# untitled.net
KiCad netlist of a schematic drawn in EAGLE
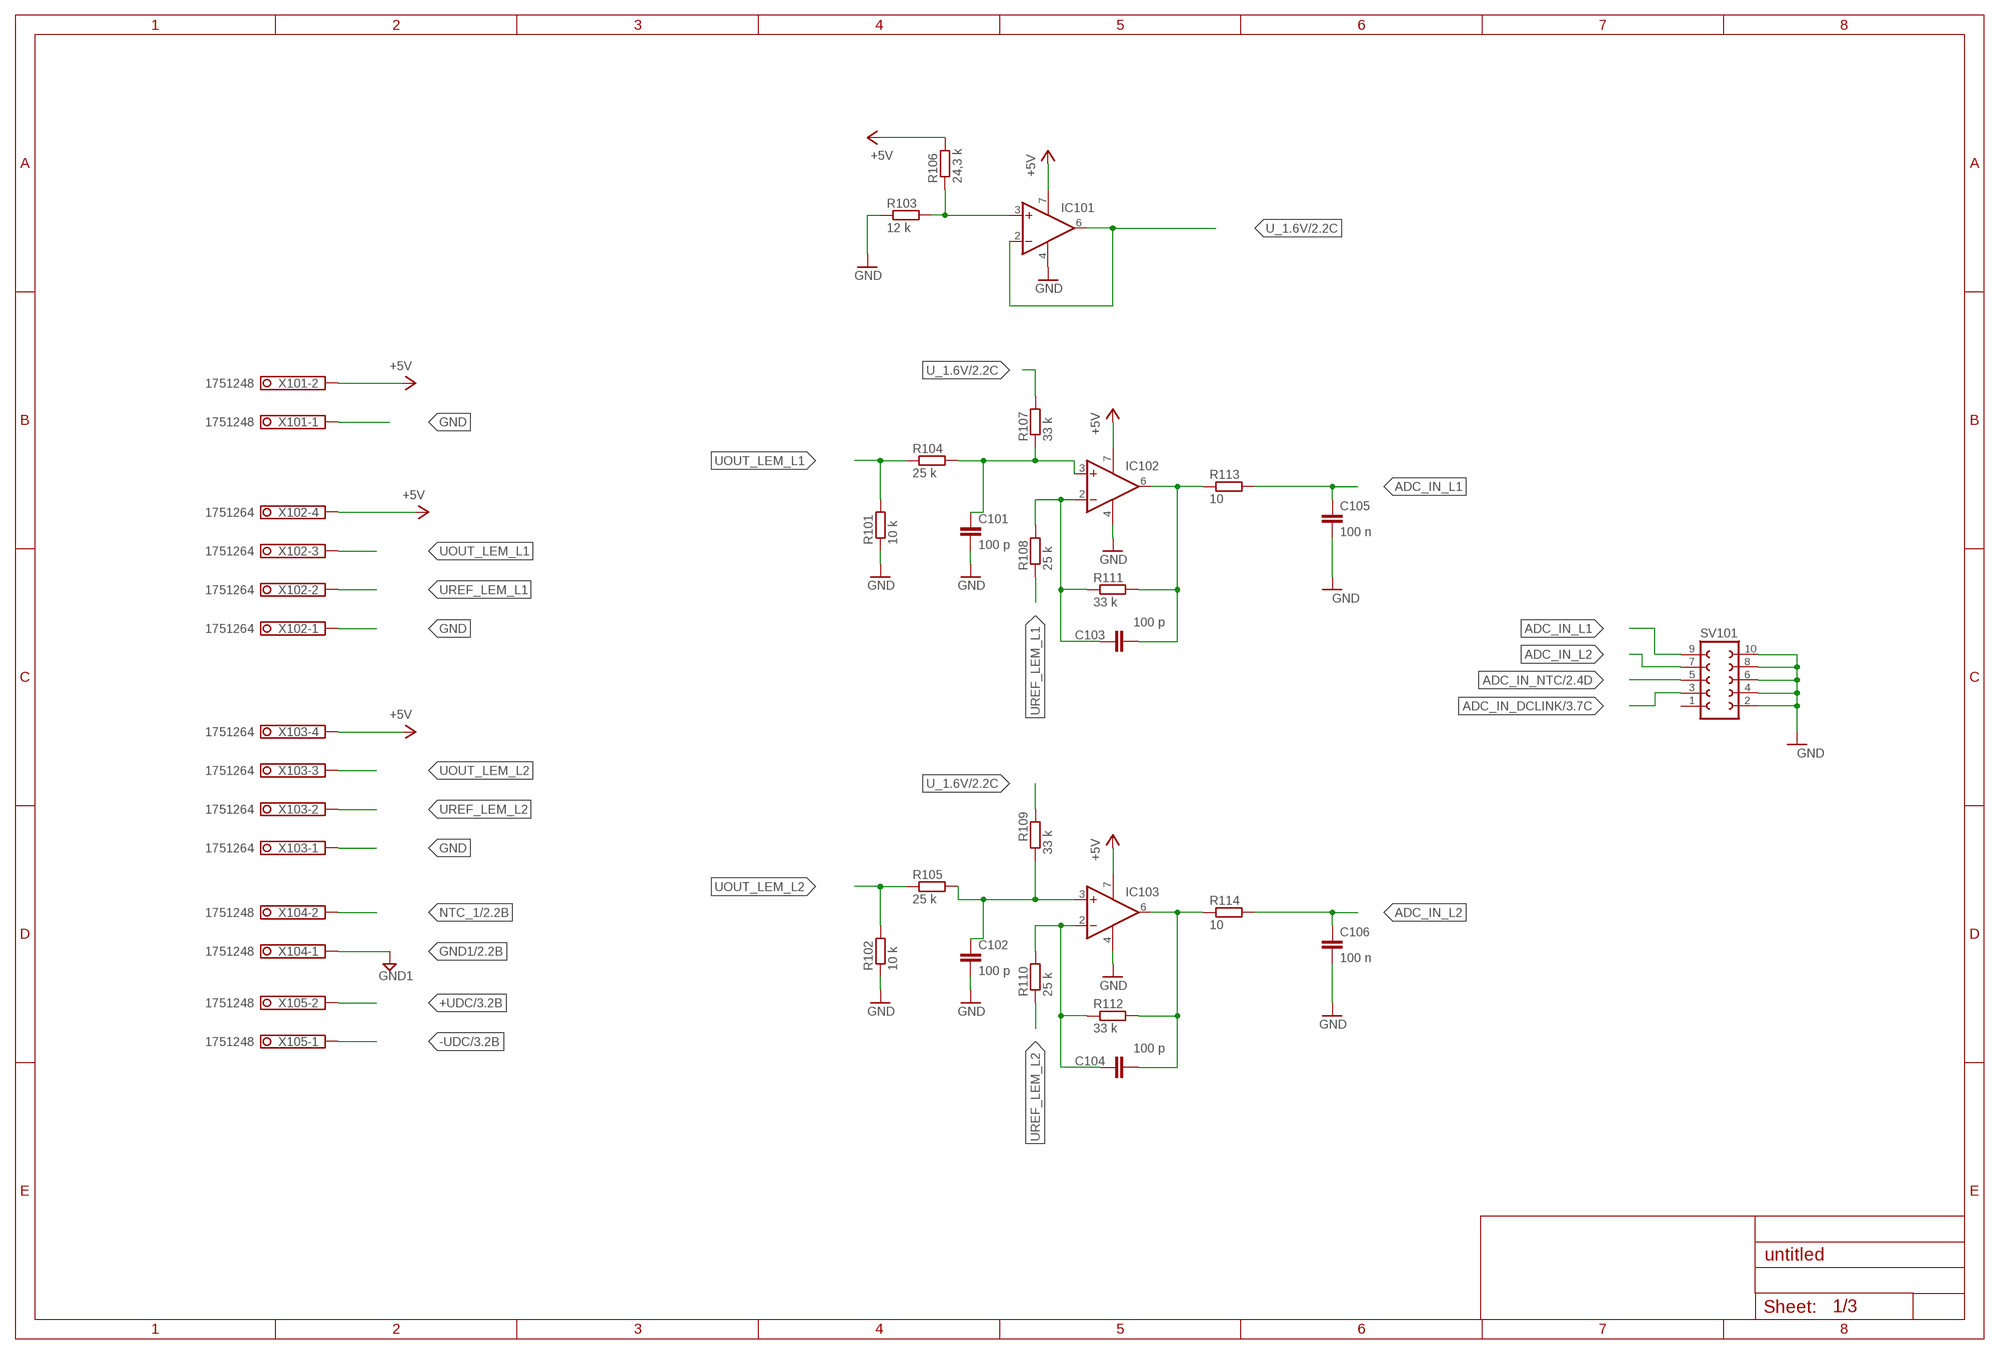
[diagram p0: schematic, sheet 1]
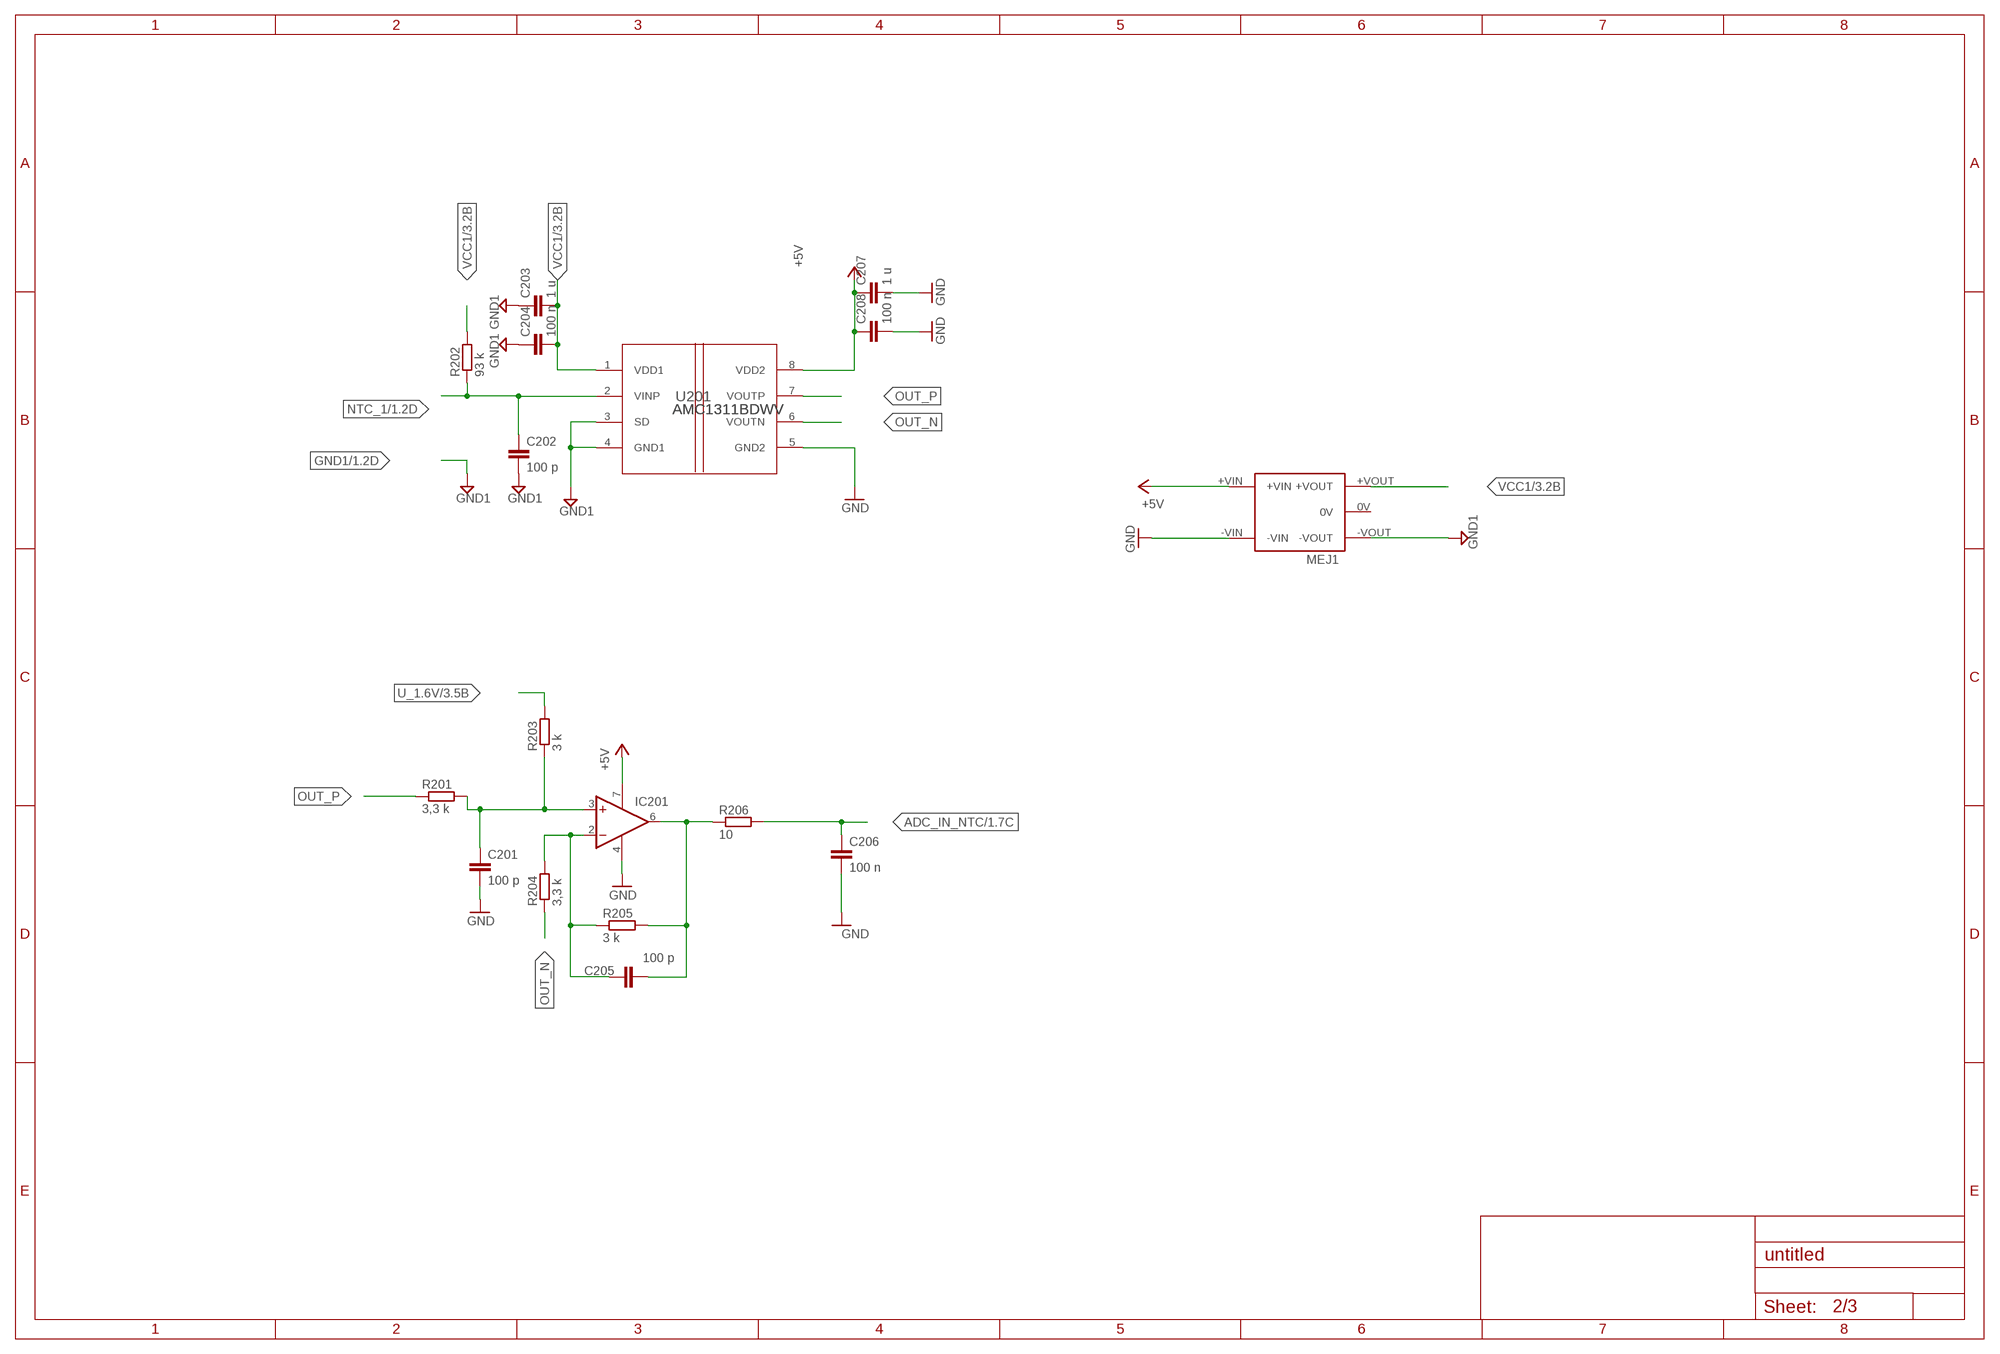
[diagram p1: schematic, sheet 2]
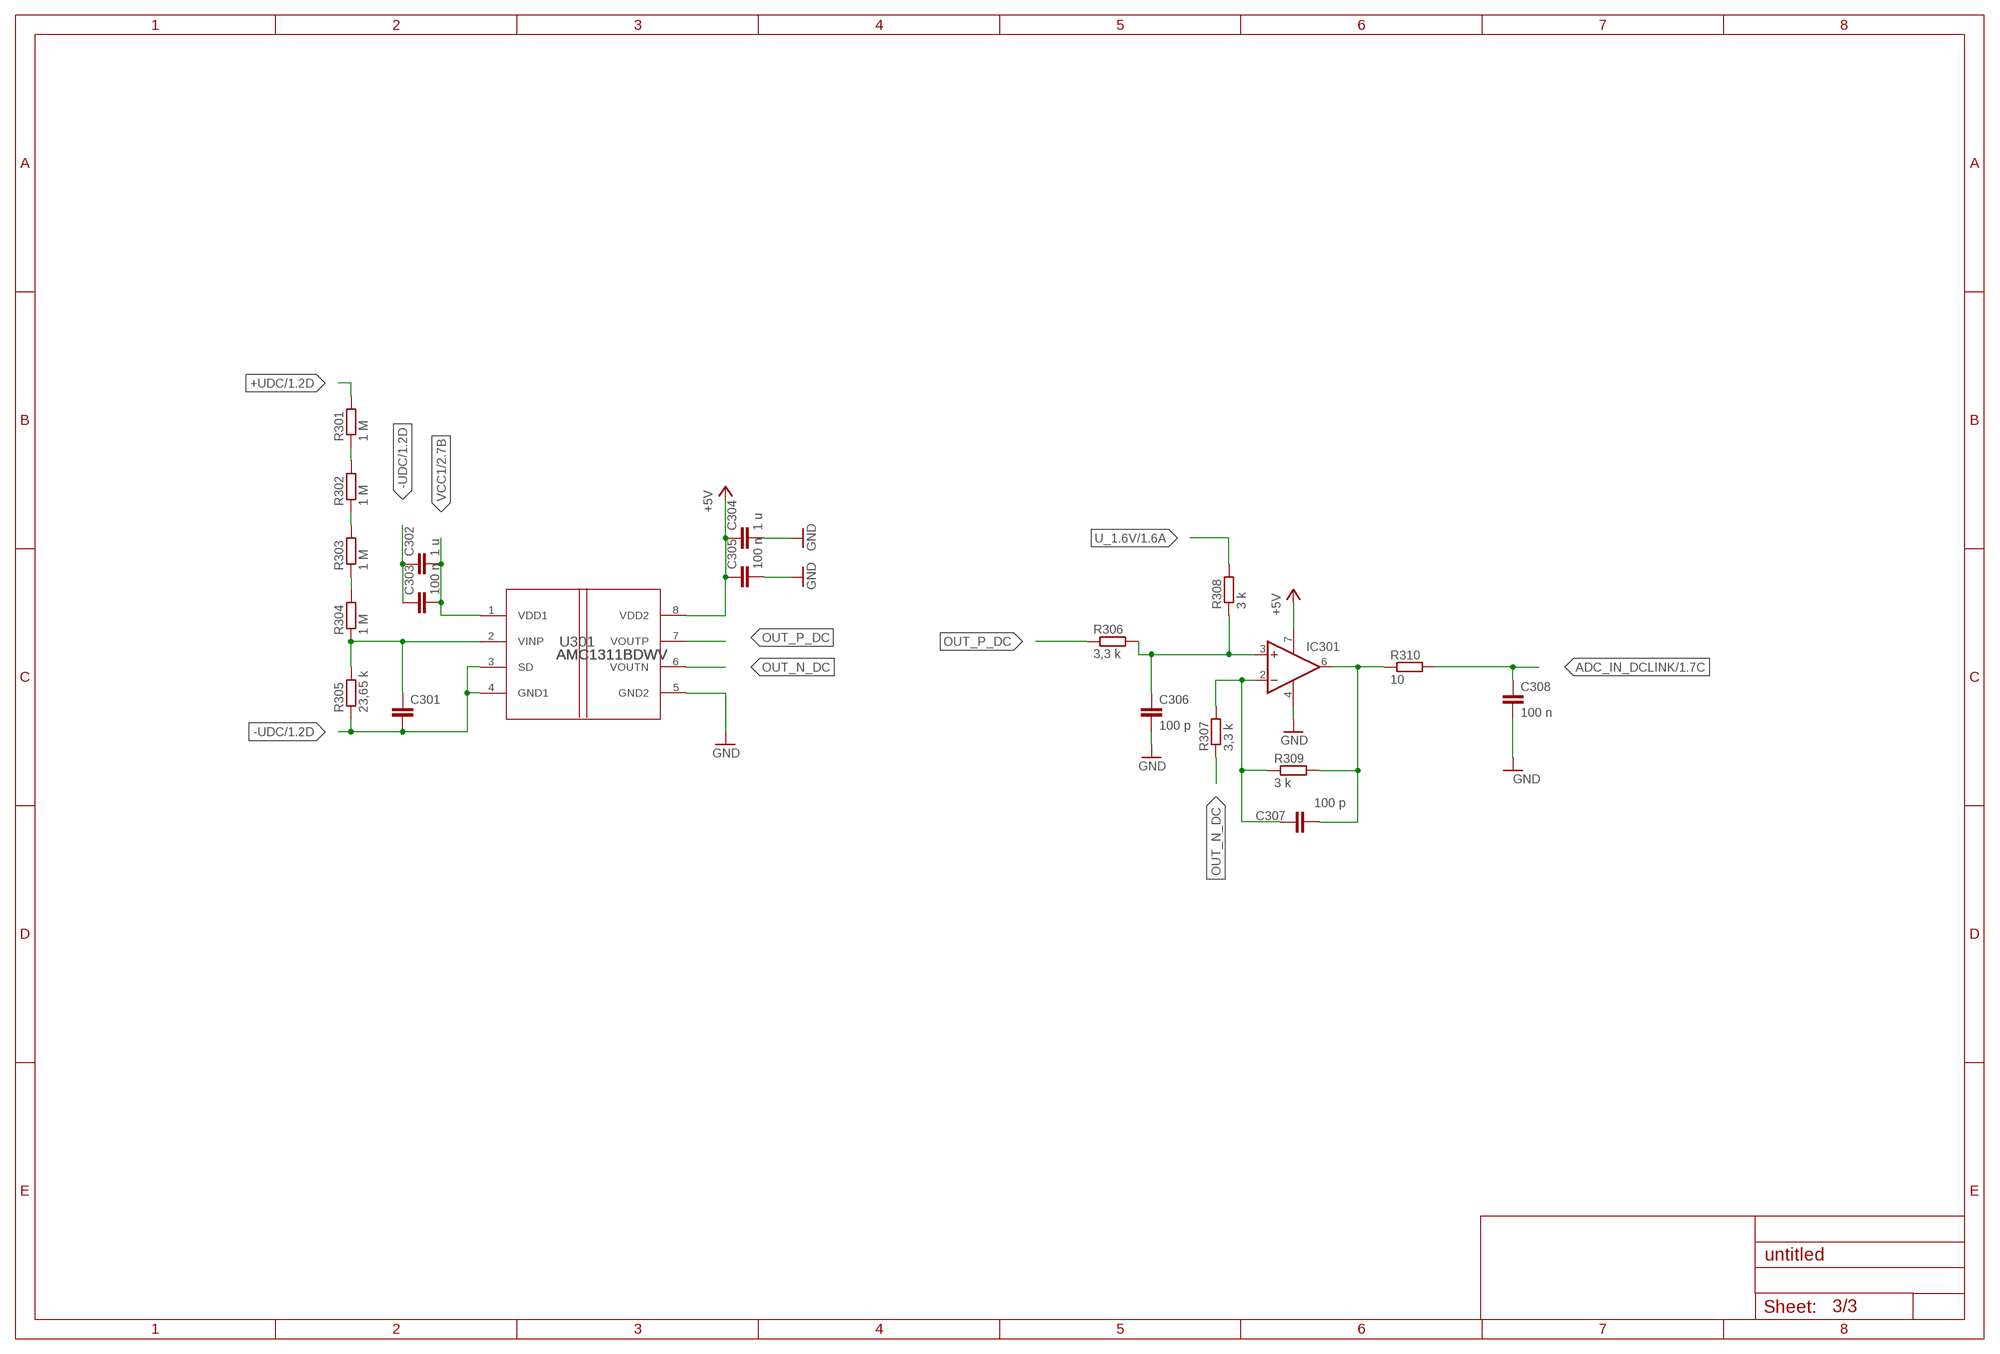
[diagram p2: schematic, sheet 3]

(export (version "E")
  (design (tool "Eeschema 10.0.6"))
  (components
    (comp (ref "C101")
      (value "100 p")
      (footprint "eagle-import:C0603")
      (libsource (lib "eagle-import") (part "C-EUC0603"))
    )
    (comp (ref "C102")
      (value "100 p")
      (footprint "eagle-import:C0603")
      (libsource (lib "eagle-import") (part "C-EUC0603"))
    )
    (comp (ref "C103")
      (value "100 p")
      (footprint "eagle-import:C0603")
      (libsource (lib "eagle-import") (part "C-EUC0603"))
    )
    (comp (ref "C104")
      (value "100 p")
      (footprint "eagle-import:C0603")
      (libsource (lib "eagle-import") (part "C-EUC0603"))
    )
    (comp (ref "C105")
      (value "100 n")
      (footprint "eagle-import:C1206")
      (libsource (lib "eagle-import") (part "C-EUC1206"))
    )
    (comp (ref "C106")
      (value "100 n")
      (footprint "eagle-import:C1206")
      (libsource (lib "eagle-import") (part "C-EUC1206"))
    )
    (comp (ref "IC101")
      (value "1AMP_P7+4D")
      (footprint "eagle-import:SO08")
      (libsource (lib "eagle-import") (part "1AMP_P7+4D"))
    )
    (comp (ref "IC102")
      (value "1AMP_P7+4D")
      (footprint "eagle-import:SO08")
      (libsource (lib "eagle-import") (part "1AMP_P7+4D"))
    )
    (comp (ref "IC103")
      (value "1AMP_P7+4D")
      (footprint "eagle-import:SO08")
      (libsource (lib "eagle-import") (part "1AMP_P7+4D"))
    )
    (comp (ref "R101")
      (value "10 k")
      (footprint "eagle-import:R0402")
      (libsource (lib "eagle-import") (part "R-EU_R0402"))
    )
    (comp (ref "R102")
      (value "10 k")
      (footprint "eagle-import:R0402")
      (libsource (lib "eagle-import") (part "R-EU_R0402"))
    )
    (comp (ref "R103")
      (value "12 k")
      (footprint "eagle-import:R0402")
      (libsource (lib "eagle-import") (part "R-EU_R0402"))
    )
    (comp (ref "R104")
      (value "25 k")
      (footprint "eagle-import:R0402")
      (libsource (lib "eagle-import") (part "R-EU_R0402"))
    )
    (comp (ref "R105")
      (value "25 k")
      (footprint "eagle-import:R0402")
      (libsource (lib "eagle-import") (part "R-EU_R0402"))
    )
    (comp (ref "R106")
      (value "24,3 k")
      (footprint "eagle-import:R0402")
      (libsource (lib "eagle-import") (part "R-EU_R0402"))
    )
    (comp (ref "R107")
      (value "33 k")
      (footprint "eagle-import:R0402")
      (libsource (lib "eagle-import") (part "R-EU_R0402"))
    )
    (comp (ref "R108")
      (value "25 k")
      (footprint "eagle-import:R0402")
      (libsource (lib "eagle-import") (part "R-EU_R0402"))
    )
    (comp (ref "R109")
      (value "33 k")
      (footprint "eagle-import:R0402")
      (libsource (lib "eagle-import") (part "R-EU_R0402"))
    )
    (comp (ref "R110")
      (value "25 k")
      (footprint "eagle-import:R0402")
      (libsource (lib "eagle-import") (part "R-EU_R0402"))
    )
    (comp (ref "R111")
      (value "33 k")
      (footprint "eagle-import:R0402")
      (libsource (lib "eagle-import") (part "R-EU_R0402"))
    )
    (comp (ref "R112")
      (value "33 k")
      (footprint "eagle-import:R0402")
      (libsource (lib "eagle-import") (part "R-EU_R0402"))
    )
    (comp (ref "R113")
      (value "10")
      (footprint "eagle-import:R0402")
      (libsource (lib "eagle-import") (part "R-EU_R0402"))
    )
    (comp (ref "R114")
      (value "10")
      (footprint "eagle-import:R0402")
      (libsource (lib "eagle-import") (part "R-EU_R0402"))
    )
    (comp (ref "SV101")
      (value "FE05-2")
      (footprint "eagle-import:FE05-2")
      (libsource (lib "eagle-import") (part "FE05-2"))
    )
    (comp (ref "X101")
      (value "1751248")
      (footprint "eagle-import:1751248")
      (libsource (lib "eagle-import") (part "1751248"))
    )
    (comp (ref "X102")
      (value "1751264")
      (footprint "eagle-import:1751264")
      (libsource (lib "eagle-import") (part "1751264"))
    )
    (comp (ref "X103")
      (value "1751264")
      (footprint "eagle-import:1751264")
      (libsource (lib "eagle-import") (part "1751264"))
    )
    (comp (ref "X104")
      (value "1751248")
      (footprint "eagle-import:1751248")
      (libsource (lib "eagle-import") (part "1751248"))
    )
    (comp (ref "X105")
      (value "1751248")
      (footprint "eagle-import:1751248")
      (libsource (lib "eagle-import") (part "1751248"))
    )
    (comp (ref "C301")
      (value "100 p")
      (footprint "eagle-import:C0603")
      (libsource (lib "eagle-import") (part "C-EUC0603"))
    )
    (comp (ref "C302")
      (value "1 u")
      (footprint "eagle-import:C0805")
      (libsource (lib "eagle-import") (part "C-EUC0805"))
    )
    (comp (ref "C303")
      (value "100 n")
      (footprint "eagle-import:C0805")
      (libsource (lib "eagle-import") (part "C-EUC0805"))
    )
    (comp (ref "C304")
      (value "1 u")
      (footprint "eagle-import:C0805")
      (libsource (lib "eagle-import") (part "C-EUC0805"))
    )
    (comp (ref "C305")
      (value "100 n")
      (footprint "eagle-import:C0805")
      (libsource (lib "eagle-import") (part "C-EUC0805"))
    )
    (comp (ref "C306")
      (value "100 p")
      (footprint "eagle-import:C0603")
      (libsource (lib "eagle-import") (part "C-EUC0603"))
    )
    (comp (ref "C307")
      (value "100 p")
      (footprint "eagle-import:C0603")
      (libsource (lib "eagle-import") (part "C-EUC0603"))
    )
    (comp (ref "C308")
      (value "100 n")
      (footprint "eagle-import:C1206")
      (libsource (lib "eagle-import") (part "C-EUC1206"))
    )
    (comp (ref "IC301")
      (value "1AMP_P7+4D")
      (footprint "eagle-import:SO08")
      (libsource (lib "eagle-import") (part "1AMP_P7+4D"))
    )
    (comp (ref "R301")
      (value "1 M")
      (footprint "eagle-import:R0603")
      (libsource (lib "eagle-import") (part "R-EU_R0603"))
    )
    (comp (ref "R302")
      (value "1 M")
      (footprint "eagle-import:R0603")
      (libsource (lib "eagle-import") (part "R-EU_R0603"))
    )
    (comp (ref "R303")
      (value "1 M")
      (footprint "eagle-import:R0603")
      (libsource (lib "eagle-import") (part "R-EU_R0603"))
    )
    (comp (ref "R304")
      (value "1 M")
      (footprint "eagle-import:R0603")
      (libsource (lib "eagle-import") (part "R-EU_R0603"))
    )
    (comp (ref "R305")
      (value "23,65 k")
      (footprint "eagle-import:R0603")
      (libsource (lib "eagle-import") (part "R-EU_R0603"))
    )
    (comp (ref "R306")
      (value "3,3 k")
      (footprint "eagle-import:R0402")
      (libsource (lib "eagle-import") (part "R-EU_R0402"))
    )
    (comp (ref "R307")
      (value "3,3 k")
      (footprint "eagle-import:R0402")
      (libsource (lib "eagle-import") (part "R-EU_R0402"))
    )
    (comp (ref "R308")
      (value "3 k")
      (footprint "eagle-import:R0402")
      (libsource (lib "eagle-import") (part "R-EU_R0402"))
    )
    (comp (ref "R309")
      (value "3 k")
      (footprint "eagle-import:R0402")
      (libsource (lib "eagle-import") (part "R-EU_R0402"))
    )
    (comp (ref "R310")
      (value "10")
      (footprint "eagle-import:R0402")
      (libsource (lib "eagle-import") (part "R-EU_R0402"))
    )
    (comp (ref "U301")
      (value "AMC1311BDWV")
      (footprint "eagle-import:DWV0008A")
      (fields (field (name "COPYRIGHT") "Copyright (C) 2024 Ultra Librarian. All rights reserved."))
      (libsource (lib "eagle-import") (part "AMC1311BDWV"))
    )
    (comp (ref "C201")
      (value "100 p")
      (footprint "eagle-import:C0603")
      (libsource (lib "eagle-import") (part "C-EUC0603"))
    )
    (comp (ref "C202")
      (value "100 p")
      (footprint "eagle-import:C0603")
      (libsource (lib "eagle-import") (part "C-EUC0603"))
    )
    (comp (ref "C203")
      (value "1 u")
      (footprint "eagle-import:C0805")
      (libsource (lib "eagle-import") (part "C-EUC0805"))
    )
    (comp (ref "C204")
      (value "100 n")
      (footprint "eagle-import:C0805")
      (libsource (lib "eagle-import") (part "C-EUC0805"))
    )
    (comp (ref "C205")
      (value "100 p")
      (footprint "eagle-import:C0603")
      (libsource (lib "eagle-import") (part "C-EUC0603"))
    )
    (comp (ref "C206")
      (value "100 n")
      (footprint "eagle-import:C1206")
      (libsource (lib "eagle-import") (part "C-EUC1206"))
    )
    (comp (ref "C207")
      (value "1 u")
      (footprint "eagle-import:C0805")
      (libsource (lib "eagle-import") (part "C-EUC0805"))
    )
    (comp (ref "C208")
      (value "100 n")
      (footprint "eagle-import:C0805")
      (libsource (lib "eagle-import") (part "C-EUC0805"))
    )
    (comp (ref "IC201")
      (value "1AMP_P7+4D")
      (footprint "eagle-import:SO08")
      (libsource (lib "eagle-import") (part "1AMP_P7+4D"))
    )
    (comp (ref "MEJ1")
      (value "MEJ1")
      (footprint "eagle-import:MEJ1")
      (libsource (lib "eagle-import") (part "MEJ1"))
    )
    (comp (ref "R201")
      (value "3,3 k")
      (footprint "eagle-import:R0402")
      (libsource (lib "eagle-import") (part "R-EU_R0402"))
    )
    (comp (ref "R202")
      (value "93 k")
      (footprint "eagle-import:R0402")
      (libsource (lib "eagle-import") (part "R-EU_R0402"))
    )
    (comp (ref "R203")
      (value "3 k")
      (footprint "eagle-import:R0402")
      (libsource (lib "eagle-import") (part "R-EU_R0402"))
    )
    (comp (ref "R204")
      (value "3,3 k")
      (footprint "eagle-import:R0402")
      (libsource (lib "eagle-import") (part "R-EU_R0402"))
    )
    (comp (ref "R205")
      (value "3 k")
      (footprint "eagle-import:R0402")
      (libsource (lib "eagle-import") (part "R-EU_R0402"))
    )
    (comp (ref "R206")
      (value "10")
      (footprint "eagle-import:R0402")
      (libsource (lib "eagle-import") (part "R-EU_R0402"))
    )
    (comp (ref "U201")
      (value "AMC1311BDWV")
      (footprint "eagle-import:DWV0008A")
      (fields (field (name "COPYRIGHT") "Copyright (C) 2024 Ultra Librarian. All rights reserved."))
      (libsource (lib "eagle-import") (part "AMC1311BDWV"))
    )
  )
  (nets
    (net (code "1") (name "+5V") (class "Default")
      (node (ref "C207") (pin "1") (pinfunction "1_1") (pintype "passive"))
      (node (ref "C208") (pin "1") (pinfunction "1_1") (pintype "passive"))
      (node (ref "C304") (pin "1") (pinfunction "1_1") (pintype "passive"))
      (node (ref "C305") (pin "1") (pinfunction "1_1") (pintype "passive"))
      (node (ref "IC101") (pin "7") (pinfunction "V+_7") (pintype "power_in"))
      (node (ref "IC102") (pin "7") (pinfunction "V+_7") (pintype "power_in"))
      (node (ref "IC103") (pin "7") (pinfunction "V+_7") (pintype "power_in"))
      (node (ref "IC201") (pin "7") (pinfunction "V+_7") (pintype "power_in"))
      (node (ref "IC301") (pin "7") (pinfunction "V+_7") (pintype "power_in"))
      (node (ref "MEJ1") (pin "+VIN") (pinfunction "+VIN_+VIN") (pintype "bidirectional"))
      (node (ref "R106") (pin "2") (pinfunction "2_2") (pintype "passive"))
      (node (ref "U201") (pin "8") (pinfunction "VDD2_8") (pintype "power_in"))
      (node (ref "U301") (pin "8") (pinfunction "VDD2_8") (pintype "power_in"))
      (node (ref "X101") (pin "2") (pinfunction "K_2") (pintype "passive"))
      (node (ref "X102") (pin "4") (pinfunction "K_4") (pintype "passive"))
      (node (ref "X103") (pin "4") (pinfunction "K_4") (pintype "passive"))
    )
    (net (code "2") (name "+UDC") (class "Default")
      (node (ref "R301") (pin "2") (pinfunction "2_2") (pintype "passive"))
      (node (ref "X105") (pin "2") (pinfunction "K_2") (pintype "passive"))
    )
    (net (code "3") (name "-UDC") (class "Default")
      (node (ref "C301") (pin "2") (pinfunction "2_2") (pintype "passive"))
      (node (ref "C302") (pin "1") (pinfunction "1_1") (pintype "passive"))
      (node (ref "C303") (pin "1") (pinfunction "1_1") (pintype "passive"))
      (node (ref "R305") (pin "1") (pinfunction "1_1") (pintype "passive"))
      (node (ref "U301") (pin "3") (pinfunction "SD_3") (pintype "input"))
      (node (ref "U301") (pin "4") (pinfunction "GND1_4") (pintype "power_in"))
      (node (ref "X105") (pin "1") (pinfunction "K_1") (pintype "passive"))
    )
    (net (code "4") (name "ADC_IN_DCLINK") (class "Default")
      (node (ref "C308") (pin "1") (pinfunction "1_1") (pintype "passive"))
      (node (ref "R310") (pin "2") (pinfunction "2_2") (pintype "passive"))
      (node (ref "SV101") (pin "3") (pinfunction "3_3") (pintype "passive"))
    )
    (net (code "5") (name "ADC_IN_L1") (class "Default")
      (node (ref "C105") (pin "1") (pinfunction "1_1") (pintype "passive"))
      (node (ref "R113") (pin "2") (pinfunction "2_2") (pintype "passive"))
      (node (ref "SV101") (pin "9") (pinfunction "9_9") (pintype "passive"))
    )
    (net (code "6") (name "ADC_IN_L2") (class "Default")
      (node (ref "C106") (pin "1") (pinfunction "1_1") (pintype "passive"))
      (node (ref "R114") (pin "2") (pinfunction "2_2") (pintype "passive"))
      (node (ref "SV101") (pin "7") (pinfunction "7_7") (pintype "passive"))
    )
    (net (code "7") (name "ADC_IN_NTC") (class "Default")
      (node (ref "C206") (pin "1") (pinfunction "1_1") (pintype "passive"))
      (node (ref "R206") (pin "2") (pinfunction "2_2") (pintype "passive"))
      (node (ref "SV101") (pin "5") (pinfunction "5_5") (pintype "passive"))
    )
    (net (code "8") (name "GND") (class "Default")
      (node (ref "C101") (pin "2") (pinfunction "2_2") (pintype "passive"))
      (node (ref "C102") (pin "2") (pinfunction "2_2") (pintype "passive"))
      (node (ref "C105") (pin "2") (pinfunction "2_2") (pintype "passive"))
      (node (ref "C106") (pin "2") (pinfunction "2_2") (pintype "passive"))
      (node (ref "C201") (pin "2") (pinfunction "2_2") (pintype "passive"))
      (node (ref "C206") (pin "2") (pinfunction "2_2") (pintype "passive"))
      (node (ref "C207") (pin "2") (pinfunction "2_2") (pintype "passive"))
      (node (ref "C208") (pin "2") (pinfunction "2_2") (pintype "passive"))
      (node (ref "C304") (pin "2") (pinfunction "2_2") (pintype "passive"))
      (node (ref "C305") (pin "2") (pinfunction "2_2") (pintype "passive"))
      (node (ref "C306") (pin "2") (pinfunction "2_2") (pintype "passive"))
      (node (ref "C308") (pin "2") (pinfunction "2_2") (pintype "passive"))
      (node (ref "IC101") (pin "4") (pinfunction "V-_4") (pintype "power_in"))
      (node (ref "IC102") (pin "4") (pinfunction "V-_4") (pintype "power_in"))
      (node (ref "IC103") (pin "4") (pinfunction "V-_4") (pintype "power_in"))
      (node (ref "IC201") (pin "4") (pinfunction "V-_4") (pintype "power_in"))
      (node (ref "IC301") (pin "4") (pinfunction "V-_4") (pintype "power_in"))
      (node (ref "MEJ1") (pin "-VIN") (pinfunction "-VIN_-VIN") (pintype "bidirectional"))
      (node (ref "R101") (pin "1") (pinfunction "1_1") (pintype "passive"))
      (node (ref "R102") (pin "1") (pinfunction "1_1") (pintype "passive"))
      (node (ref "R103") (pin "1") (pinfunction "1_1") (pintype "passive"))
      (node (ref "SV101") (pin "10") (pinfunction "10_10") (pintype "passive"))
      (node (ref "SV101") (pin "2") (pinfunction "2_2") (pintype "passive"))
      (node (ref "SV101") (pin "4") (pinfunction "4_4") (pintype "passive"))
      (node (ref "SV101") (pin "6") (pinfunction "6_6") (pintype "passive"))
      (node (ref "SV101") (pin "8") (pinfunction "8_8") (pintype "passive"))
      (node (ref "U201") (pin "5") (pinfunction "GND2_5") (pintype "power_in"))
      (node (ref "U301") (pin "5") (pinfunction "GND2_5") (pintype "power_in"))
      (node (ref "X101") (pin "1") (pinfunction "K_1") (pintype "passive"))
      (node (ref "X102") (pin "1") (pinfunction "K_1") (pintype "passive"))
      (node (ref "X103") (pin "1") (pinfunction "K_1") (pintype "passive"))
    )
    (net (code "9") (name "GND1") (class "Default")
      (node (ref "C202") (pin "2") (pinfunction "2_2") (pintype "passive"))
      (node (ref "C203") (pin "1") (pinfunction "1_1") (pintype "passive"))
      (node (ref "C204") (pin "1") (pinfunction "1_1") (pintype "passive"))
      (node (ref "MEJ1") (pin "-VOUT") (pinfunction "-VOUT_-VOUT") (pintype "bidirectional"))
      (node (ref "U201") (pin "3") (pinfunction "SD_3") (pintype "input"))
      (node (ref "U201") (pin "4") (pinfunction "GND1_4") (pintype "power_in"))
      (node (ref "X104") (pin "1") (pinfunction "K_1") (pintype "passive"))
    )
    (net (code "10") (name "NTC_1") (class "Default")
      (node (ref "C202") (pin "1") (pinfunction "1_1") (pintype "passive"))
      (node (ref "R202") (pin "1") (pinfunction "1_1") (pintype "passive"))
      (node (ref "U201") (pin "2") (pinfunction "VINP_2") (pintype "input"))
      (node (ref "X104") (pin "2") (pinfunction "K_2") (pintype "passive"))
    )
    (net (code "11") (name "Net-(IC101-+IN)") (class "Default")
      (node (ref "IC101") (pin "3") (pinfunction "+IN_3") (pintype "input"))
      (node (ref "R103") (pin "2") (pinfunction "2_2") (pintype "passive"))
      (node (ref "R106") (pin "1") (pinfunction "1_1") (pintype "passive"))
    )
    (net (code "12") (name "Net-(IC102-+IN)") (class "Default")
      (node (ref "C101") (pin "1") (pinfunction "1_1") (pintype "passive"))
      (node (ref "IC102") (pin "3") (pinfunction "+IN_3") (pintype "input"))
      (node (ref "R104") (pin "2") (pinfunction "2_2") (pintype "passive"))
      (node (ref "R107") (pin "1") (pinfunction "1_1") (pintype "passive"))
    )
    (net (code "13") (name "Net-(IC102--IN)") (class "Default")
      (node (ref "C103") (pin "1") (pinfunction "1_1") (pintype "passive"))
      (node (ref "IC102") (pin "2") (pinfunction "-IN_2") (pintype "input"))
      (node (ref "R108") (pin "2") (pinfunction "2_2") (pintype "passive"))
      (node (ref "R111") (pin "1") (pinfunction "1_1") (pintype "passive"))
    )
    (net (code "14") (name "Net-(IC102-OUT)") (class "Default")
      (node (ref "C103") (pin "2") (pinfunction "2_2") (pintype "passive"))
      (node (ref "IC102") (pin "6") (pinfunction "OUT_6") (pintype "output"))
      (node (ref "R111") (pin "2") (pinfunction "2_2") (pintype "passive"))
      (node (ref "R113") (pin "1") (pinfunction "1_1") (pintype "passive"))
    )
    (net (code "15") (name "Net-(IC103-+IN)") (class "Default")
      (node (ref "C102") (pin "1") (pinfunction "1_1") (pintype "passive"))
      (node (ref "IC103") (pin "3") (pinfunction "+IN_3") (pintype "input"))
      (node (ref "R105") (pin "2") (pinfunction "2_2") (pintype "passive"))
      (node (ref "R109") (pin "1") (pinfunction "1_1") (pintype "passive"))
    )
    (net (code "16") (name "Net-(IC103--IN)") (class "Default")
      (node (ref "C104") (pin "1") (pinfunction "1_1") (pintype "passive"))
      (node (ref "IC103") (pin "2") (pinfunction "-IN_2") (pintype "input"))
      (node (ref "R110") (pin "2") (pinfunction "2_2") (pintype "passive"))
      (node (ref "R112") (pin "1") (pinfunction "1_1") (pintype "passive"))
    )
    (net (code "17") (name "Net-(IC103-OUT)") (class "Default")
      (node (ref "C104") (pin "2") (pinfunction "2_2") (pintype "passive"))
      (node (ref "IC103") (pin "6") (pinfunction "OUT_6") (pintype "output"))
      (node (ref "R112") (pin "2") (pinfunction "2_2") (pintype "passive"))
      (node (ref "R114") (pin "1") (pinfunction "1_1") (pintype "passive"))
    )
    (net (code "18") (name "Net-(IC201-+IN)") (class "Default")
      (node (ref "C201") (pin "1") (pinfunction "1_1") (pintype "passive"))
      (node (ref "IC201") (pin "3") (pinfunction "+IN_3") (pintype "input"))
      (node (ref "R201") (pin "2") (pinfunction "2_2") (pintype "passive"))
      (node (ref "R203") (pin "1") (pinfunction "1_1") (pintype "passive"))
    )
    (net (code "19") (name "Net-(IC201--IN)") (class "Default")
      (node (ref "C205") (pin "1") (pinfunction "1_1") (pintype "passive"))
      (node (ref "IC201") (pin "2") (pinfunction "-IN_2") (pintype "input"))
      (node (ref "R204") (pin "2") (pinfunction "2_2") (pintype "passive"))
      (node (ref "R205") (pin "1") (pinfunction "1_1") (pintype "passive"))
    )
    (net (code "20") (name "Net-(IC201-OUT)") (class "Default")
      (node (ref "C205") (pin "2") (pinfunction "2_2") (pintype "passive"))
      (node (ref "IC201") (pin "6") (pinfunction "OUT_6") (pintype "output"))
      (node (ref "R205") (pin "2") (pinfunction "2_2") (pintype "passive"))
      (node (ref "R206") (pin "1") (pinfunction "1_1") (pintype "passive"))
    )
    (net (code "21") (name "Net-(IC301-+IN)") (class "Default")
      (node (ref "C306") (pin "1") (pinfunction "1_1") (pintype "passive"))
      (node (ref "IC301") (pin "3") (pinfunction "+IN_3") (pintype "input"))
      (node (ref "R306") (pin "2") (pinfunction "2_2") (pintype "passive"))
      (node (ref "R308") (pin "1") (pinfunction "1_1") (pintype "passive"))
    )
    (net (code "22") (name "Net-(IC301--IN)") (class "Default")
      (node (ref "C307") (pin "1") (pinfunction "1_1") (pintype "passive"))
      (node (ref "IC301") (pin "2") (pinfunction "-IN_2") (pintype "input"))
      (node (ref "R307") (pin "2") (pinfunction "2_2") (pintype "passive"))
      (node (ref "R309") (pin "1") (pinfunction "1_1") (pintype "passive"))
    )
    (net (code "23") (name "Net-(IC301-OUT)") (class "Default")
      (node (ref "C307") (pin "2") (pinfunction "2_2") (pintype "passive"))
      (node (ref "IC301") (pin "6") (pinfunction "OUT_6") (pintype "output"))
      (node (ref "R309") (pin "2") (pinfunction "2_2") (pintype "passive"))
      (node (ref "R310") (pin "1") (pinfunction "1_1") (pintype "passive"))
    )
    (net (code "24") (name "Net-(R301-Pad1)") (class "Default")
      (node (ref "R301") (pin "1") (pinfunction "1_1") (pintype "passive"))
      (node (ref "R302") (pin "2") (pinfunction "2_2") (pintype "passive"))
    )
    (net (code "25") (name "Net-(R302-Pad1)") (class "Default")
      (node (ref "R302") (pin "1") (pinfunction "1_1") (pintype "passive"))
      (node (ref "R303") (pin "2") (pinfunction "2_2") (pintype "passive"))
    )
    (net (code "26") (name "Net-(R303-Pad1)") (class "Default")
      (node (ref "R303") (pin "1") (pinfunction "1_1") (pintype "passive"))
      (node (ref "R304") (pin "2") (pinfunction "2_2") (pintype "passive"))
    )
    (net (code "27") (name "Net-(U301-VINP)") (class "Default")
      (node (ref "C301") (pin "1") (pinfunction "1_1") (pintype "passive"))
      (node (ref "R304") (pin "1") (pinfunction "1_1") (pintype "passive"))
      (node (ref "R305") (pin "2") (pinfunction "2_2") (pintype "passive"))
      (node (ref "U301") (pin "2") (pinfunction "VINP_2") (pintype "input"))
    )
    (net (code "28") (name "OUT_N") (class "Default")
      (node (ref "R204") (pin "1") (pinfunction "1_1") (pintype "passive"))
      (node (ref "U201") (pin "6") (pinfunction "VOUTN_6") (pintype "output"))
    )
    (net (code "29") (name "OUT_N_DC") (class "Default")
      (node (ref "R307") (pin "1") (pinfunction "1_1") (pintype "passive"))
      (node (ref "U301") (pin "6") (pinfunction "VOUTN_6") (pintype "output"))
    )
    (net (code "30") (name "OUT_P") (class "Default")
      (node (ref "R201") (pin "1") (pinfunction "1_1") (pintype "passive"))
      (node (ref "U201") (pin "7") (pinfunction "VOUTP_7") (pintype "output"))
    )
    (net (code "31") (name "OUT_P_DC") (class "Default")
      (node (ref "R306") (pin "1") (pinfunction "1_1") (pintype "passive"))
      (node (ref "U301") (pin "7") (pinfunction "VOUTP_7") (pintype "output"))
    )
    (net (code "32") (name "UOUT_LEM_L1") (class "Default")
      (node (ref "R101") (pin "2") (pinfunction "2_2") (pintype "passive"))
      (node (ref "R104") (pin "1") (pinfunction "1_1") (pintype "passive"))
      (node (ref "X102") (pin "3") (pinfunction "K_3") (pintype "passive"))
    )
    (net (code "33") (name "UOUT_LEM_L2") (class "Default")
      (node (ref "R102") (pin "2") (pinfunction "2_2") (pintype "passive"))
      (node (ref "R105") (pin "1") (pinfunction "1_1") (pintype "passive"))
      (node (ref "X103") (pin "3") (pinfunction "K_3") (pintype "passive"))
    )
    (net (code "34") (name "UREF_LEM_L1") (class "Default")
      (node (ref "R108") (pin "1") (pinfunction "1_1") (pintype "passive"))
      (node (ref "X102") (pin "2") (pinfunction "K_2") (pintype "passive"))
    )
    (net (code "35") (name "UREF_LEM_L2") (class "Default")
      (node (ref "R110") (pin "1") (pinfunction "1_1") (pintype "passive"))
      (node (ref "X103") (pin "2") (pinfunction "K_2") (pintype "passive"))
    )
    (net (code "36") (name "U_1.6V") (class "Default")
      (node (ref "IC101") (pin "2") (pinfunction "-IN_2") (pintype "input"))
      (node (ref "IC101") (pin "6") (pinfunction "OUT_6") (pintype "output"))
      (node (ref "R107") (pin "2") (pinfunction "2_2") (pintype "passive"))
      (node (ref "R109") (pin "2") (pinfunction "2_2") (pintype "passive"))
      (node (ref "R203") (pin "2") (pinfunction "2_2") (pintype "passive"))
      (node (ref "R308") (pin "2") (pinfunction "2_2") (pintype "passive"))
    )
    (net (code "37") (name "VCC1") (class "Default")
      (node (ref "C203") (pin "2") (pinfunction "2_2") (pintype "passive"))
      (node (ref "C204") (pin "2") (pinfunction "2_2") (pintype "passive"))
      (node (ref "C302") (pin "2") (pinfunction "2_2") (pintype "passive"))
      (node (ref "C303") (pin "2") (pinfunction "2_2") (pintype "passive"))
      (node (ref "MEJ1") (pin "+VOUT") (pinfunction "+VOUT_+VOUT") (pintype "bidirectional"))
      (node (ref "R202") (pin "2") (pinfunction "2_2") (pintype "passive"))
      (node (ref "U201") (pin "1") (pinfunction "VDD1_1") (pintype "power_in"))
      (node (ref "U301") (pin "1") (pinfunction "VDD1_1") (pintype "power_in"))
    )
    (net (code "38") (name "unconnected-(MEJ1-Pad0V)") (class "Default")
      (node (ref "MEJ1") (pin "0V") (pinfunction "0V_0V") (pintype "bidirectional"))
    )
    (net (code "39") (name "unconnected-(SV101-Pad1)") (class "Default")
      (node (ref "SV101") (pin "1") (pinfunction "1_1") (pintype "passive"))
    )
  )
)
